# MCU_Power.net
KiCad netlist of a schematic drawn in Altium Designer
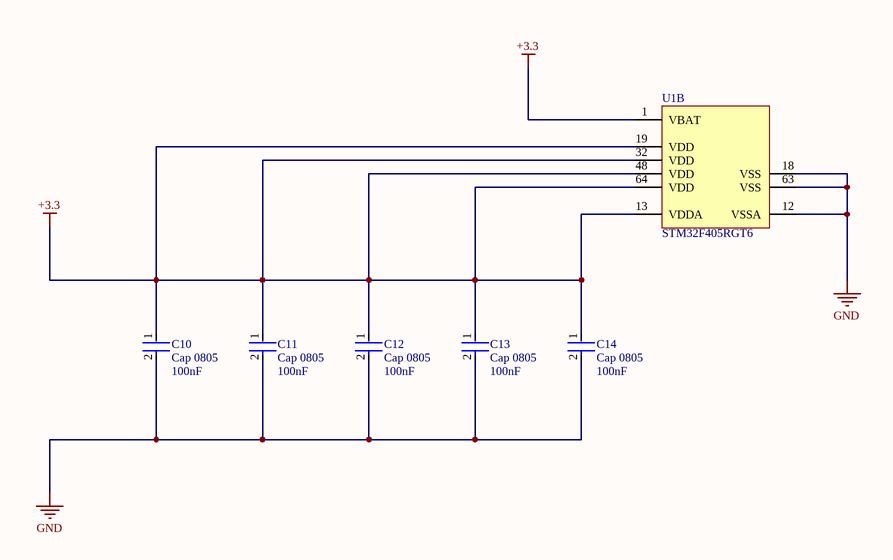
[diagram p0: MCU Power.SchDoc]

(export (version "E")
  (design (tool "Eeschema 10.0.6"))
  (components
    (comp (ref "C10")
      (value "Cap 0805")
      (footprint "FP-GRM216-0_1-IPC_C")
      (description "Capacitor")
      (fields (field (name "ALTIUM_VALUE") "100nF"))
      (libsource (lib "Altium Content Vault") (part "236180d848d6139a670b325ea6854c9"))
    )
    (comp (ref "C11")
      (value "Cap 0805")
      (footprint "FP-GRM216-0_1-IPC_C")
      (description "Capacitor")
      (fields (field (name "ALTIUM_VALUE") "100nF"))
      (libsource (lib "Altium Content Vault") (part "236180d848d6139a670b325ea6854c9"))
    )
    (comp (ref "C12")
      (value "Cap 0805")
      (footprint "FP-GRM216-0_1-IPC_C")
      (description "Capacitor")
      (fields (field (name "ALTIUM_VALUE") "100nF"))
      (libsource (lib "Altium Content Vault") (part "236180d848d6139a670b325ea6854c9"))
    )
    (comp (ref "C13")
      (value "Cap 0805")
      (footprint "FP-GRM216-0_1-IPC_C")
      (description "Capacitor")
      (fields (field (name "ALTIUM_VALUE") "100nF"))
      (libsource (lib "Altium Content Vault") (part "236180d848d6139a670b325ea6854c9"))
    )
    (comp (ref "C14")
      (value "Cap 0805")
      (footprint "FP-GRM216-0_1-IPC_C")
      (description "Capacitor")
      (fields (field (name "ALTIUM_VALUE") "100nF"))
      (libsource (lib "Altium Content Vault") (part "236180d848d6139a670b325ea6854c9"))
    )
    (comp (ref "U1")
      (value "STM32F405RGT6")
      (footprint "STM-LQFP64_V")
      (fields (field (name "MANUFACTURER") "STMicroelectronics"))
      (libsource (lib "Altium Content Vault") (part "MC-ARM-STM32F4X5-SQ64"))
    )
  )
  (nets
    (net (code "1") (name "+3.3") (class "Default")
      (node (ref "C10") (pin "1") (pinfunction "1_1") (pintype "passive"))
      (node (ref "C11") (pin "1") (pinfunction "1_1") (pintype "passive"))
      (node (ref "C12") (pin "1") (pinfunction "1_1") (pintype "passive"))
      (node (ref "C13") (pin "1") (pinfunction "1_1") (pintype "passive"))
      (node (ref "C14") (pin "1") (pinfunction "1_1") (pintype "passive"))
      (node (ref "U1") (pin "1") (pinfunction "VBAT_1") (pintype "power_in"))
      (node (ref "U1") (pin "13") (pinfunction "VDDA_13") (pintype "power_in"))
      (node (ref "U1") (pin "19") (pinfunction "VDD_19") (pintype "power_in"))
      (node (ref "U1") (pin "32") (pinfunction "VDD_32") (pintype "power_in"))
      (node (ref "U1") (pin "48") (pinfunction "VDD_48") (pintype "power_in"))
      (node (ref "U1") (pin "64") (pinfunction "VDD_64") (pintype "power_in"))
    )
    (net (code "2") (name "GND") (class "Default")
      (node (ref "C10") (pin "2") (pinfunction "2_2") (pintype "passive"))
      (node (ref "C11") (pin "2") (pinfunction "2_2") (pintype "passive"))
      (node (ref "C12") (pin "2") (pinfunction "2_2") (pintype "passive"))
      (node (ref "C13") (pin "2") (pinfunction "2_2") (pintype "passive"))
      (node (ref "C14") (pin "2") (pinfunction "2_2") (pintype "passive"))
      (node (ref "U1") (pin "12") (pinfunction "VSSA_12") (pintype "power_in"))
      (node (ref "U1") (pin "18") (pinfunction "VSS_18") (pintype "power_in"))
      (node (ref "U1") (pin "63") (pinfunction "VSS_63") (pintype "power_in"))
    )
  )
)
